# Sheet1.net
KiCad netlist of a schematic drawn in Altium Designer
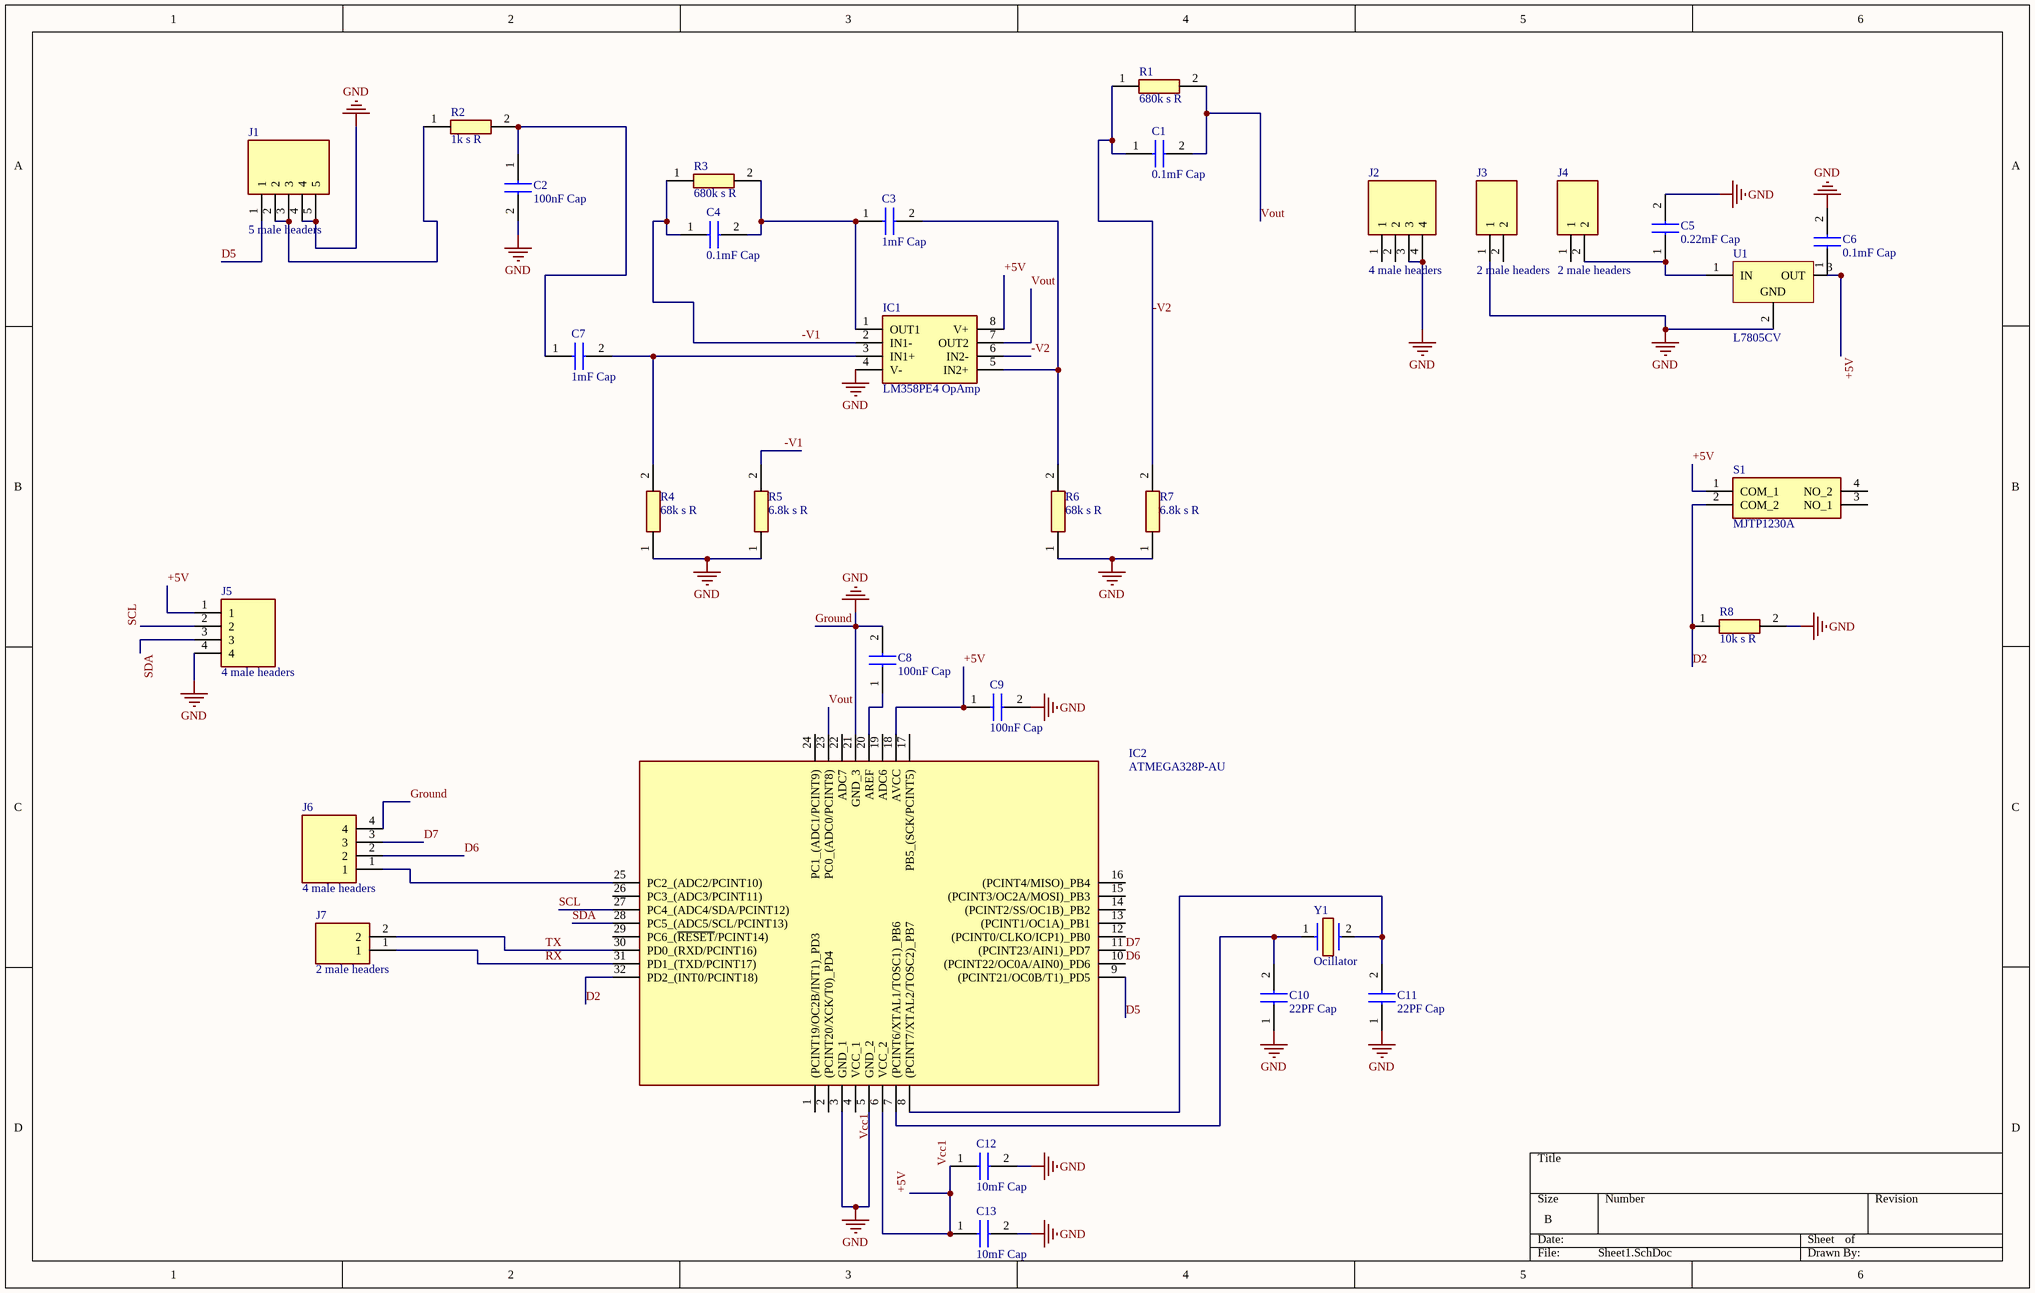
[diagram p0: Sheet1.SchDoc]

(export (version "E")
  (design (tool "Eeschema 10.0.6"))
  (components
    (comp (ref "C1")
      (value "0.1mF Cap")
      (footprint "SamacSys:VY2332M41Y5US63V7")
      (description "Capacitor")
      (fields
        (field (name "MANUFACTURER_PART_NUMBER") "VY2332M41Y5US63V7")
        (field (name "MOUSER PART NUMBER") "72-VY2332M41Y5US63V7")
      )
      (libsource (lib "Schlib1") (part "0.1mF Cap"))
    )
    (comp (ref "C2")
      (value "100nF Cap")
      (footprint "SamacSys:VY2332M41Y5US63V7")
      (description "Capacitor")
      (fields
        (field (name "MANUFACTURER_PART_NUMBER") "VY2332M41Y5US63V7")
        (field (name "MOUSER PART NUMBER") "72-VY2332M41Y5US63V7")
      )
      (libsource (lib "Schlib1") (part "100nF Cap"))
    )
    (comp (ref "C3")
      (value "1mF Cap")
      (footprint "SamacSys:VY2332M41Y5US63V7")
      (description "Capacitor")
      (fields
        (field (name "MANUFACTURER_PART_NUMBER") "VY2332M41Y5US63V7")
        (field (name "MOUSER PART NUMBER") "72-VY2332M41Y5US63V7")
      )
      (libsource (lib "Schlib1") (part "1mF Cap"))
    )
    (comp (ref "C4")
      (value "0.1mF Cap")
      (footprint "SamacSys:VY2332M41Y5US63V7")
      (description "Capacitor")
      (fields
        (field (name "MANUFACTURER_PART_NUMBER") "VY2332M41Y5US63V7")
        (field (name "MOUSER PART NUMBER") "72-VY2332M41Y5US63V7")
      )
      (libsource (lib "Schlib1") (part "0.1mF Cap"))
    )
    (comp (ref "C5")
      (value "0.22mF Cap")
      (footprint "SamacSys:VY2332M41Y5US63V7")
      (description "Capacitor")
      (fields
        (field (name "MANUFACTURER_PART_NUMBER") "VY2332M41Y5US63V7")
        (field (name "MOUSER PART NUMBER") "72-VY2332M41Y5US63V7")
      )
      (libsource (lib "Schlib1") (part "0.22mF Cap"))
    )
    (comp (ref "C6")
      (value "0.1mF Cap")
      (footprint "SamacSys:VY2332M41Y5US63V7")
      (description "Capacitor")
      (fields
        (field (name "MANUFACTURER_PART_NUMBER") "VY2332M41Y5US63V7")
        (field (name "MOUSER PART NUMBER") "72-VY2332M41Y5US63V7")
      )
      (libsource (lib "Schlib1") (part "0.1mF Cap"))
    )
    (comp (ref "C7")
      (value "1mF Cap")
      (footprint "SamacSys:VY2332M41Y5US63V7")
      (description "Capacitor")
      (fields
        (field (name "MANUFACTURER_PART_NUMBER") "VY2332M41Y5US63V7")
        (field (name "MOUSER PART NUMBER") "72-VY2332M41Y5US63V7")
      )
      (libsource (lib "Schlib1") (part "1mF Cap"))
    )
    (comp (ref "C8")
      (value "100nF Cap")
      (footprint "SamacSys:VY2332M41Y5US63V7")
      (description "Capacitor")
      (fields
        (field (name "MANUFACTURER_PART_NUMBER") "VY2332M41Y5US63V7")
        (field (name "MOUSER PART NUMBER") "72-VY2332M41Y5US63V7")
      )
      (libsource (lib "Schlib1") (part "100nF Cap"))
    )
    (comp (ref "C9")
      (value "100nF Cap")
      (footprint "SamacSys:VY2332M41Y5US63V7")
      (description "Capacitor")
      (fields
        (field (name "MANUFACTURER_PART_NUMBER") "VY2332M41Y5US63V7")
        (field (name "MOUSER PART NUMBER") "72-VY2332M41Y5US63V7")
      )
      (libsource (lib "Schlib1") (part "100nF Cap"))
    )
    (comp (ref "C10")
      (value "22PF Cap")
      (footprint "SamacSys:VY2332M41Y5US63V7")
      (description "Capacitor")
      (fields
        (field (name "MANUFACTURER_PART_NUMBER") "VY2332M41Y5US63V7")
        (field (name "MOUSER PART NUMBER") "72-VY2332M41Y5US63V7")
      )
      (libsource (lib "Schlib1") (part "22PF Cap"))
    )
    (comp (ref "C11")
      (value "22PF Cap")
      (footprint "SamacSys:VY2332M41Y5US63V7")
      (description "Capacitor")
      (fields
        (field (name "MANUFACTURER_PART_NUMBER") "VY2332M41Y5US63V7")
        (field (name "MOUSER PART NUMBER") "72-VY2332M41Y5US63V7")
      )
      (libsource (lib "Schlib1") (part "22PF Cap"))
    )
    (comp (ref "C12")
      (value "10mF Cap")
      (footprint "SamacSys:VY2332M41Y5US63V7")
      (description "Capacitor")
      (fields
        (field (name "MANUFACTURER_PART_NUMBER") "VY2332M41Y5US63V7")
        (field (name "MOUSER PART NUMBER") "72-VY2332M41Y5US63V7")
      )
      (libsource (lib "Schlib1") (part "10mF Cap"))
    )
    (comp (ref "C13")
      (value "10mF Cap")
      (footprint "SamacSys:VY2332M41Y5US63V7")
      (description "Capacitor")
      (fields
        (field (name "MANUFACTURER_PART_NUMBER") "VY2332M41Y5US63V7")
        (field (name "MOUSER PART NUMBER") "72-VY2332M41Y5US63V7")
      )
      (libsource (lib "Schlib1") (part "10mF Cap"))
    )
    (comp (ref "IC1")
      (value "LM358PE4 OpAmp")
      (footprint "SamacSys:DIP794W53P254L959H508Q8N")
      (description "Integrated Circuit")
      (fields
        (field (name "MANUFACTURER_PART_NUMBER") "LM358PE4")
        (field (name "MOUSER PART NUMBER") "595-LM358PE4")
      )
      (libsource (lib "Schlib1") (part "LM358PE4 OpAmp"))
    )
    (comp (ref "IC2")
      (value "ATMEGA328P-AU")
      (footprint "SamacSys:QFP80P900X900X120-32N")
      (description "Integrated Circuit")
      (fields (field (name "MOUSER PART NUMBER") "556-ATMEGA328P-AU"))
      (libsource (lib "Schlib1") (part "ATMEGA328P-AU"))
    )
    (comp (ref "J1")
      (value "5 male headers")
      (footprint "SamacSys:HDRV5W63P0X254_1X5_1270X254X970P")
      (description "Connector")
      (fields
        (field (name "MANUFACTURER_PART_NUMBER") "825433-5")
        (field (name "MOUSER PART NUMBER") "571-825433-5")
      )
      (libsource (lib "Schlib1") (part "5 male headers"))
    )
    (comp (ref "J2")
      (value "4 male headers")
      (footprint "SamacSys:HDRV4W63P0X254_1X4_1016X250X950P")
      (description "Connector")
      (fields
        (field (name "MANUFACTURER_PART_NUMBER") "826629-4")
        (field (name "MOUSER PART NUMBER") "571-826629-4")
      )
      (libsource (lib "") (part "4 male headers_2"))
    )
    (comp (ref "J3")
      (value "2 male headers")
      (footprint "SamacSys:HDRV2W63P0X254_1X2_508X250X970P")
      (description "Connector")
      (fields
        (field (name "MANUFACTURER_PART_NUMBER") "826926-2")
        (field (name "MOUSER PART NUMBER") "571-826926-2")
      )
      (libsource (lib "Schlib1") (part "2 male headers"))
    )
    (comp (ref "J4")
      (value "2 male headers")
      (footprint "SamacSys:HDRV2W63P0X254_1X2_508X250X970P")
      (description "Connector")
      (fields
        (field (name "MANUFACTURER_PART_NUMBER") "826926-2")
        (field (name "MOUSER PART NUMBER") "571-826926-2")
      )
      (libsource (lib "Schlib1") (part "2 male headers"))
    )
    (comp (ref "J5")
      (value "4 male headers")
      (footprint "SamacSys:HDRV4W63P0X254_1X4_1016X250X950P")
      (description "Connector")
      (fields
        (field (name "MANUFACTURER_PART_NUMBER") "826629-4")
        (field (name "MOUSER PART NUMBER") "571-826629-4")
      )
      (libsource (lib "Schlib1") (part "4 male headers"))
    )
    (comp (ref "J6")
      (value "4 male headers")
      (footprint "SamacSys:HDRV4W63P0X254_1X4_1016X250X950P")
      (description "Connector")
      (fields
        (field (name "MANUFACTURER_PART_NUMBER") "826629-4")
        (field (name "MOUSER PART NUMBER") "571-826629-4")
      )
      (libsource (lib "") (part "4 male headers_1"))
    )
    (comp (ref "J7")
      (value "2 male headers")
      (footprint "SamacSys:HDRV2W63P0X254_1X2_508X250X970P")
      (description "Connector")
      (fields
        (field (name "MANUFACTURER_PART_NUMBER") "826926-2")
        (field (name "MOUSER PART NUMBER") "571-826926-2")
      )
      (libsource (lib "") (part "2 male headers_1"))
    )
    (comp (ref "R1")
      (value "680k s R")
      (footprint "SamacSys:ERJUP6")
      (description "Resistor")
      (fields
        (field (name "MANUFACTURER_PART_NUMBER") "ERJ-UP6F5760V")
        (field (name "MOUSER PART NUMBER") "667-ERJ-UP6F5760V")
      )
      (libsource (lib "Schlib1") (part "680k s R"))
    )
    (comp (ref "R2")
      (value "1k s R")
      (footprint "SamacSys:ERJUP6")
      (description "Resistor")
      (fields
        (field (name "MANUFACTURER_PART_NUMBER") "ERJ-UP6F5760V")
        (field (name "MOUSER PART NUMBER") "667-ERJ-UP6F5760V")
      )
      (libsource (lib "Schlib1") (part "1k s R"))
    )
    (comp (ref "R3")
      (value "680k s R")
      (footprint "SamacSys:ERJUP6")
      (description "Resistor")
      (fields
        (field (name "MANUFACTURER_PART_NUMBER") "ERJ-UP6F5760V")
        (field (name "MOUSER PART NUMBER") "667-ERJ-UP6F5760V")
      )
      (libsource (lib "Schlib1") (part "680k s R"))
    )
    (comp (ref "R4")
      (value "68k s R")
      (footprint "SamacSys:ERJUP6")
      (description "Resistor")
      (fields
        (field (name "MANUFACTURER_PART_NUMBER") "ERJ-UP6F5760V")
        (field (name "MOUSER PART NUMBER") "667-ERJ-UP6F5760V")
      )
      (libsource (lib "Schlib1") (part "68k s R"))
    )
    (comp (ref "R5")
      (value "6.8k s R")
      (footprint "SamacSys:ERJUP6")
      (description "Resistor")
      (fields
        (field (name "MANUFACTURER_PART_NUMBER") "ERJ-UP6F5760V")
        (field (name "MOUSER PART NUMBER") "667-ERJ-UP6F5760V")
      )
      (libsource (lib "Schlib1") (part "6.8k s R"))
    )
    (comp (ref "R6")
      (value "68k s R")
      (footprint "SamacSys:ERJUP6")
      (description "Resistor")
      (fields
        (field (name "MANUFACTURER_PART_NUMBER") "ERJ-UP6F5760V")
        (field (name "MOUSER PART NUMBER") "667-ERJ-UP6F5760V")
      )
      (libsource (lib "Schlib1") (part "68k s R"))
    )
    (comp (ref "R7")
      (value "6.8k s R")
      (footprint "SamacSys:ERJUP6")
      (description "Resistor")
      (fields
        (field (name "MANUFACTURER_PART_NUMBER") "ERJ-UP6F5760V")
        (field (name "MOUSER PART NUMBER") "667-ERJ-UP6F5760V")
      )
      (libsource (lib "Schlib1") (part "6.8k s R"))
    )
    (comp (ref "R8")
      (value "10k s R")
      (footprint "SamacSys:ERJUP6")
      (description "Resistor")
      (fields
        (field (name "MANUFACTURER_PART_NUMBER") "ERJ-UP6F5760V")
        (field (name "MOUSER PART NUMBER") "667-ERJ-UP6F5760V")
      )
      (libsource (lib "Schlib1") (part "10k s R"))
    )
    (comp (ref "S1")
      (value "MJTP1230A")
      (footprint "SamacSys:MJTP1230A")
      (description "Switch")
      (fields (field (name "MOUSER PART NUMBER") "642-MJTP1230A"))
      (libsource (lib "Schlib1") (part "MJTP1230A"))
    )
    (comp (ref "U1")
      (value "L7805CV")
      (footprint "TO220")
      (description "Positive Voltage Regulator, 5V, 3-Pin TO-220")
      (libsource (lib "Altium Content Vault") (part "PM-REG-L4940-SIL3"))
    )
    (comp (ref "Y1")
      (value "Ocillator")
      (footprint "SamacSys:XT9S20ANA8M")
      (description "Crystal or Oscillator")
      (fields
        (field (name "MANUFACTURER_PART_NUMBER") "XT9S20ANA8M")
        (field (name "MOUSER PART NUMBER") "73-XT49S800-20")
      )
      (libsource (lib "Schlib1") (part "Ocillator"))
    )
  )
  (nets
    (net (code "1") (name "/+5V") (class "Default")
      (node (ref "C12") (pin "1") (pinfunction "1_1") (pintype "passive"))
      (node (ref "C13") (pin "1") (pinfunction "1_1") (pintype "passive"))
      (node (ref "C6") (pin "1") (pinfunction "1_1") (pintype "passive"))
      (node (ref "C9") (pin "1") (pinfunction "1_1") (pintype "passive"))
      (node (ref "IC1") (pin "8") (pinfunction "V+_8") (pintype "passive"))
      (node (ref "IC2") (pin "18") (pinfunction "AVCC_18") (pintype "passive"))
      (node (ref "IC2") (pin "4") (pinfunction "VCC_1_4") (pintype "passive"))
      (node (ref "IC2") (pin "6") (pinfunction "VCC_2_6") (pintype "passive"))
      (node (ref "J5") (pin "1") (pinfunction "1_1") (pintype "passive"))
      (node (ref "S1") (pin "1") (pinfunction "COM_1_1") (pintype "passive"))
      (node (ref "U1") (pin "3") (pinfunction "OUT_3") (pintype "power_in"))
    )
    (net (code "2") (name "/-V1") (class "Default")
      (node (ref "C4") (pin "1") (pinfunction "1_1") (pintype "passive"))
      (node (ref "IC1") (pin "2") (pinfunction "IN1-_2") (pintype "passive"))
      (node (ref "R3") (pin "1") (pinfunction "1_1") (pintype "passive"))
      (node (ref "R5") (pin "2") (pinfunction "2_2") (pintype "passive"))
    )
    (net (code "3") (name "/-V2") (class "Default")
      (node (ref "C1") (pin "1") (pinfunction "1_1") (pintype "passive"))
      (node (ref "IC1") (pin "6") (pinfunction "IN2-_6") (pintype "passive"))
      (node (ref "R1") (pin "1") (pinfunction "1_1") (pintype "passive"))
      (node (ref "R7") (pin "2") (pinfunction "2_2") (pintype "passive"))
    )
    (net (code "4") (name "/D2") (class "Default")
      (node (ref "IC2") (pin "32") (pinfunction "PD2_(INT0/PCINT18)_32") (pintype "passive"))
      (node (ref "R8") (pin "1") (pinfunction "1_1") (pintype "passive"))
      (node (ref "S1") (pin "2") (pinfunction "COM_2_2") (pintype "passive"))
    )
    (net (code "5") (name "/D5") (class "Default")
      (node (ref "IC2") (pin "9") (pinfunction "(PCINT21/OC0B/T1)_PD5_9") (pintype "passive"))
      (node (ref "J1") (pin "1") (pinfunction "1_1") (pintype "passive"))
    )
    (net (code "6") (name "/D6") (class "Default")
      (node (ref "IC2") (pin "10") (pinfunction "(PCINT22/OC0A/AIN0)_PD6_10") (pintype "passive"))
      (node (ref "J6") (pin "2") (pinfunction "2_2") (pintype "passive"))
    )
    (net (code "7") (name "/D7") (class "Default")
      (node (ref "IC2") (pin "11") (pinfunction "(PCINT23/AIN1)_PD7_11") (pintype "passive"))
      (node (ref "J6") (pin "3") (pinfunction "3_3") (pintype "passive"))
    )
    (net (code "8") (name "/RX") (class "Default")
      (node (ref "IC2") (pin "31") (pinfunction "PD1_(TXD/PCINT17)_31") (pintype "passive"))
      (node (ref "J7") (pin "1") (pinfunction "1_1") (pintype "passive"))
    )
    (net (code "9") (name "/SCL") (class "Default")
      (node (ref "IC2") (pin "27") (pinfunction "PC4_(ADC4/SDA/PCINT12)_27") (pintype "passive"))
      (node (ref "J5") (pin "2") (pinfunction "2_2") (pintype "passive"))
    )
    (net (code "10") (name "/SDA") (class "Default")
      (node (ref "IC2") (pin "28") (pinfunction "PC5_(ADC5/SCL/PCINT13)_28") (pintype "passive"))
      (node (ref "J5") (pin "3") (pinfunction "3_3") (pintype "passive"))
    )
    (net (code "11") (name "/TX") (class "Default")
      (node (ref "IC2") (pin "30") (pinfunction "PD0_(RXD/PCINT16)_30") (pintype "passive"))
      (node (ref "J7") (pin "2") (pinfunction "2_2") (pintype "passive"))
    )
    (net (code "12") (name "/Vout") (class "Default")
      (node (ref "C1") (pin "2") (pinfunction "2_2") (pintype "passive"))
      (node (ref "IC1") (pin "7") (pinfunction "OUT2_7") (pintype "passive"))
      (node (ref "IC2") (pin "23") (pinfunction "PC0_(ADC0/PCINT8)_23") (pintype "passive"))
      (node (ref "R1") (pin "2") (pinfunction "2_2") (pintype "passive"))
    )
    (net (code "13") (name "GND") (class "Default")
      (node (ref "C10") (pin "1") (pinfunction "1_1") (pintype "passive"))
      (node (ref "C11") (pin "1") (pinfunction "1_1") (pintype "passive"))
      (node (ref "C12") (pin "2") (pinfunction "2_2") (pintype "passive"))
      (node (ref "C13") (pin "2") (pinfunction "2_2") (pintype "passive"))
      (node (ref "C2") (pin "2") (pinfunction "2_2") (pintype "passive"))
      (node (ref "C5") (pin "2") (pinfunction "2_2") (pintype "passive"))
      (node (ref "C6") (pin "2") (pinfunction "2_2") (pintype "passive"))
      (node (ref "C8") (pin "2") (pinfunction "2_2") (pintype "passive"))
      (node (ref "C9") (pin "2") (pinfunction "2_2") (pintype "passive"))
      (node (ref "IC1") (pin "4") (pinfunction "V-_4") (pintype "passive"))
      (node (ref "IC2") (pin "21") (pinfunction "GND_3_21") (pintype "passive"))
      (node (ref "IC2") (pin "3") (pinfunction "GND_1_3") (pintype "passive"))
      (node (ref "IC2") (pin "5") (pinfunction "GND_2_5") (pintype "passive"))
      (node (ref "J1") (pin "4") (pinfunction "4_4") (pintype "passive"))
      (node (ref "J1") (pin "5") (pinfunction "5_5") (pintype "passive"))
      (node (ref "J2") (pin "3") (pinfunction "3_3") (pintype "passive"))
      (node (ref "J2") (pin "4") (pinfunction "4_4") (pintype "passive"))
      (node (ref "J3") (pin "1") (pinfunction "1_1") (pintype "passive"))
      (node (ref "J5") (pin "4") (pinfunction "4_4") (pintype "passive"))
      (node (ref "J6") (pin "4") (pinfunction "4_4") (pintype "passive"))
      (node (ref "R4") (pin "1") (pinfunction "1_1") (pintype "passive"))
      (node (ref "R5") (pin "1") (pinfunction "1_1") (pintype "passive"))
      (node (ref "R6") (pin "1") (pinfunction "1_1") (pintype "passive"))
      (node (ref "R7") (pin "1") (pinfunction "1_1") (pintype "passive"))
      (node (ref "R8") (pin "2") (pinfunction "2_2") (pintype "passive"))
      (node (ref "U1") (pin "2") (pinfunction "GND_2") (pintype "power_in"))
    )
    (net (code "14") (name "Net-(C2-Pad1)") (class "Default")
      (node (ref "C2") (pin "1") (pinfunction "1_1") (pintype "passive"))
      (node (ref "C7") (pin "1") (pinfunction "1_1") (pintype "passive"))
      (node (ref "R2") (pin "2") (pinfunction "2_2") (pintype "passive"))
    )
    (net (code "15") (name "Net-(IC1-IN1+)") (class "Default")
      (node (ref "C7") (pin "2") (pinfunction "2_2") (pintype "passive"))
      (node (ref "IC1") (pin "3") (pinfunction "IN1+_3") (pintype "passive"))
      (node (ref "R4") (pin "2") (pinfunction "2_2") (pintype "passive"))
    )
    (net (code "16") (name "Net-(IC1-IN2+)") (class "Default")
      (node (ref "C3") (pin "2") (pinfunction "2_2") (pintype "passive"))
      (node (ref "IC1") (pin "5") (pinfunction "IN2+_5") (pintype "passive"))
      (node (ref "R6") (pin "2") (pinfunction "2_2") (pintype "passive"))
    )
    (net (code "17") (name "Net-(IC1-OUT1)") (class "Default")
      (node (ref "C3") (pin "1") (pinfunction "1_1") (pintype "passive"))
      (node (ref "C4") (pin "2") (pinfunction "2_2") (pintype "passive"))
      (node (ref "IC1") (pin "1") (pinfunction "OUT1_1") (pintype "passive"))
      (node (ref "R3") (pin "2") (pinfunction "2_2") (pintype "passive"))
    )
    (net (code "18") (name "Net-(IC2-(PCINT6{slash}XTAL1{slash}TOSC1)_PB6)") (class "Default")
      (node (ref "C10") (pin "2") (pinfunction "2_2") (pintype "passive"))
      (node (ref "IC2") (pin "7") (pinfunction "(PCINT6/XTAL1/TOSC1)_PB6_7") (pintype "passive"))
      (node (ref "Y1") (pin "1") (pinfunction "1_1") (pintype "passive"))
    )
    (net (code "19") (name "Net-(IC2-(PCINT7{slash}XTAL2{slash}TOSC2)_PB7)") (class "Default")
      (node (ref "C11") (pin "2") (pinfunction "2_2") (pintype "passive"))
      (node (ref "IC2") (pin "8") (pinfunction "(PCINT7/XTAL2/TOSC2)_PB7_8") (pintype "passive"))
      (node (ref "Y1") (pin "2") (pinfunction "2_2") (pintype "passive"))
    )
    (net (code "20") (name "Net-(IC2-AREF)") (class "Default")
      (node (ref "C8") (pin "1") (pinfunction "1_1") (pintype "passive"))
      (node (ref "IC2") (pin "20") (pinfunction "AREF_20") (pintype "passive"))
    )
    (net (code "21") (name "Net-(IC2-PC2_(ADC2{slash}PCINT10))") (class "Default")
      (node (ref "IC2") (pin "25") (pinfunction "PC2_(ADC2/PCINT10)_25") (pintype "passive"))
      (node (ref "J6") (pin "1") (pinfunction "1_1") (pintype "passive"))
    )
    (net (code "22") (name "Net-(J1-Pad2)") (class "Default")
      (node (ref "J1") (pin "2") (pinfunction "2_2") (pintype "passive"))
      (node (ref "J1") (pin "3") (pinfunction "3_3") (pintype "passive"))
      (node (ref "R2") (pin "1") (pinfunction "1_1") (pintype "passive"))
    )
    (net (code "23") (name "Net-(U1-IN)") (class "Default")
      (node (ref "C5") (pin "1") (pinfunction "1_1") (pintype "passive"))
      (node (ref "J4") (pin "2") (pinfunction "2_2") (pintype "passive"))
      (node (ref "U1") (pin "1") (pinfunction "IN_1") (pintype "power_in"))
    )
    (net (code "24") (name "unconnected-(IC2-(PCINT0{slash}CLKO{slash}ICP1)_PB0-Pad12)") (class "Default")
      (node (ref "IC2") (pin "12") (pinfunction "(PCINT0/CLKO/ICP1)_PB0_12") (pintype "passive"))
    )
    (net (code "25") (name "unconnected-(IC2-(PCINT1{slash}OC1A)_PB1-Pad13)") (class "Default")
      (node (ref "IC2") (pin "13") (pinfunction "(PCINT1/OC1A)_PB1_13") (pintype "passive"))
    )
    (net (code "26") (name "unconnected-(IC2-(PCINT2{slash}SS{slash}OC1B)_PB2-Pad14)") (class "Default")
      (node (ref "IC2") (pin "14") (pinfunction "(PCINT2/SS/OC1B)_PB2_14") (pintype "passive"))
    )
    (net (code "27") (name "unconnected-(IC2-(PCINT3{slash}OC2A{slash}MOSI)_PB3-Pad15)") (class "Default")
      (node (ref "IC2") (pin "15") (pinfunction "(PCINT3/OC2A/MOSI)_PB3_15") (pintype "passive"))
    )
    (net (code "28") (name "unconnected-(IC2-(PCINT4{slash}MISO)_PB4-Pad16)") (class "Default")
      (node (ref "IC2") (pin "16") (pinfunction "(PCINT4/MISO)_PB4_16") (pintype "passive"))
    )
    (net (code "29") (name "unconnected-(IC2-(PCINT19{slash}OC2B{slash}INT1)_PD3-Pad1)") (class "Default")
      (node (ref "IC2") (pin "1") (pinfunction "(PCINT19/OC2B/INT1)_PD3_1") (pintype "passive"))
    )
    (net (code "30") (name "unconnected-(IC2-(PCINT20{slash}XCK{slash}T0)_PD4-Pad2)") (class "Default")
      (node (ref "IC2") (pin "2") (pinfunction "(PCINT20/XCK/T0)_PD4_2") (pintype "passive"))
    )
    (net (code "31") (name "unconnected-(IC2-ADC6-Pad19)") (class "Default")
      (node (ref "IC2") (pin "19") (pinfunction "ADC6_19") (pintype "passive"))
    )
    (net (code "32") (name "unconnected-(IC2-ADC7-Pad22)") (class "Default")
      (node (ref "IC2") (pin "22") (pinfunction "ADC7_22") (pintype "passive"))
    )
    (net (code "33") (name "unconnected-(IC2-PB5_(SCK{slash}PCINT5)-Pad17)") (class "Default")
      (node (ref "IC2") (pin "17") (pinfunction "PB5_(SCK/PCINT5)_17") (pintype "passive"))
    )
    (net (code "34") (name "unconnected-(IC2-PC1_(ADC1{slash}PCINT9)-Pad24)") (class "Default")
      (node (ref "IC2") (pin "24") (pinfunction "PC1_(ADC1/PCINT9)_24") (pintype "passive"))
    )
    (net (code "35") (name "unconnected-(IC2-PC3_(ADC3{slash}PCINT11)-Pad26)") (class "Default")
      (node (ref "IC2") (pin "26") (pinfunction "PC3_(ADC3/PCINT11)_26") (pintype "passive"))
    )
    (net (code "36") (name "unconnected-(IC2-PC6_(~{RESET}{slash}PCINT14)-Pad29)") (class "Default")
      (node (ref "IC2") (pin "29") (pinfunction "PC6_(~{RESET}/PCINT14)_29") (pintype "passive"))
    )
    (net (code "37") (name "unconnected-(J2-Pad1)") (class "Default")
      (node (ref "J2") (pin "1") (pinfunction "1_1") (pintype "passive"))
    )
    (net (code "38") (name "unconnected-(J2-Pad2)") (class "Default")
      (node (ref "J2") (pin "2") (pinfunction "2_2") (pintype "passive"))
    )
    (net (code "39") (name "unconnected-(J3-Pad2)") (class "Default")
      (node (ref "J3") (pin "2") (pinfunction "2_2") (pintype "passive"))
    )
    (net (code "40") (name "unconnected-(J4-Pad1)") (class "Default")
      (node (ref "J4") (pin "1") (pinfunction "1_1") (pintype "passive"))
    )
    (net (code "41") (name "unconnected-(S1-NO_1-Pad3)") (class "Default")
      (node (ref "S1") (pin "3") (pinfunction "NO_1_3") (pintype "passive"))
    )
    (net (code "42") (name "unconnected-(S1-NO_2-Pad4)") (class "Default")
      (node (ref "S1") (pin "4") (pinfunction "NO_2_4") (pintype "passive"))
    )
  )
)
